# i2c-4x8matrix-relays.net
KiCad netlist of a schematic drawn in EAGLE
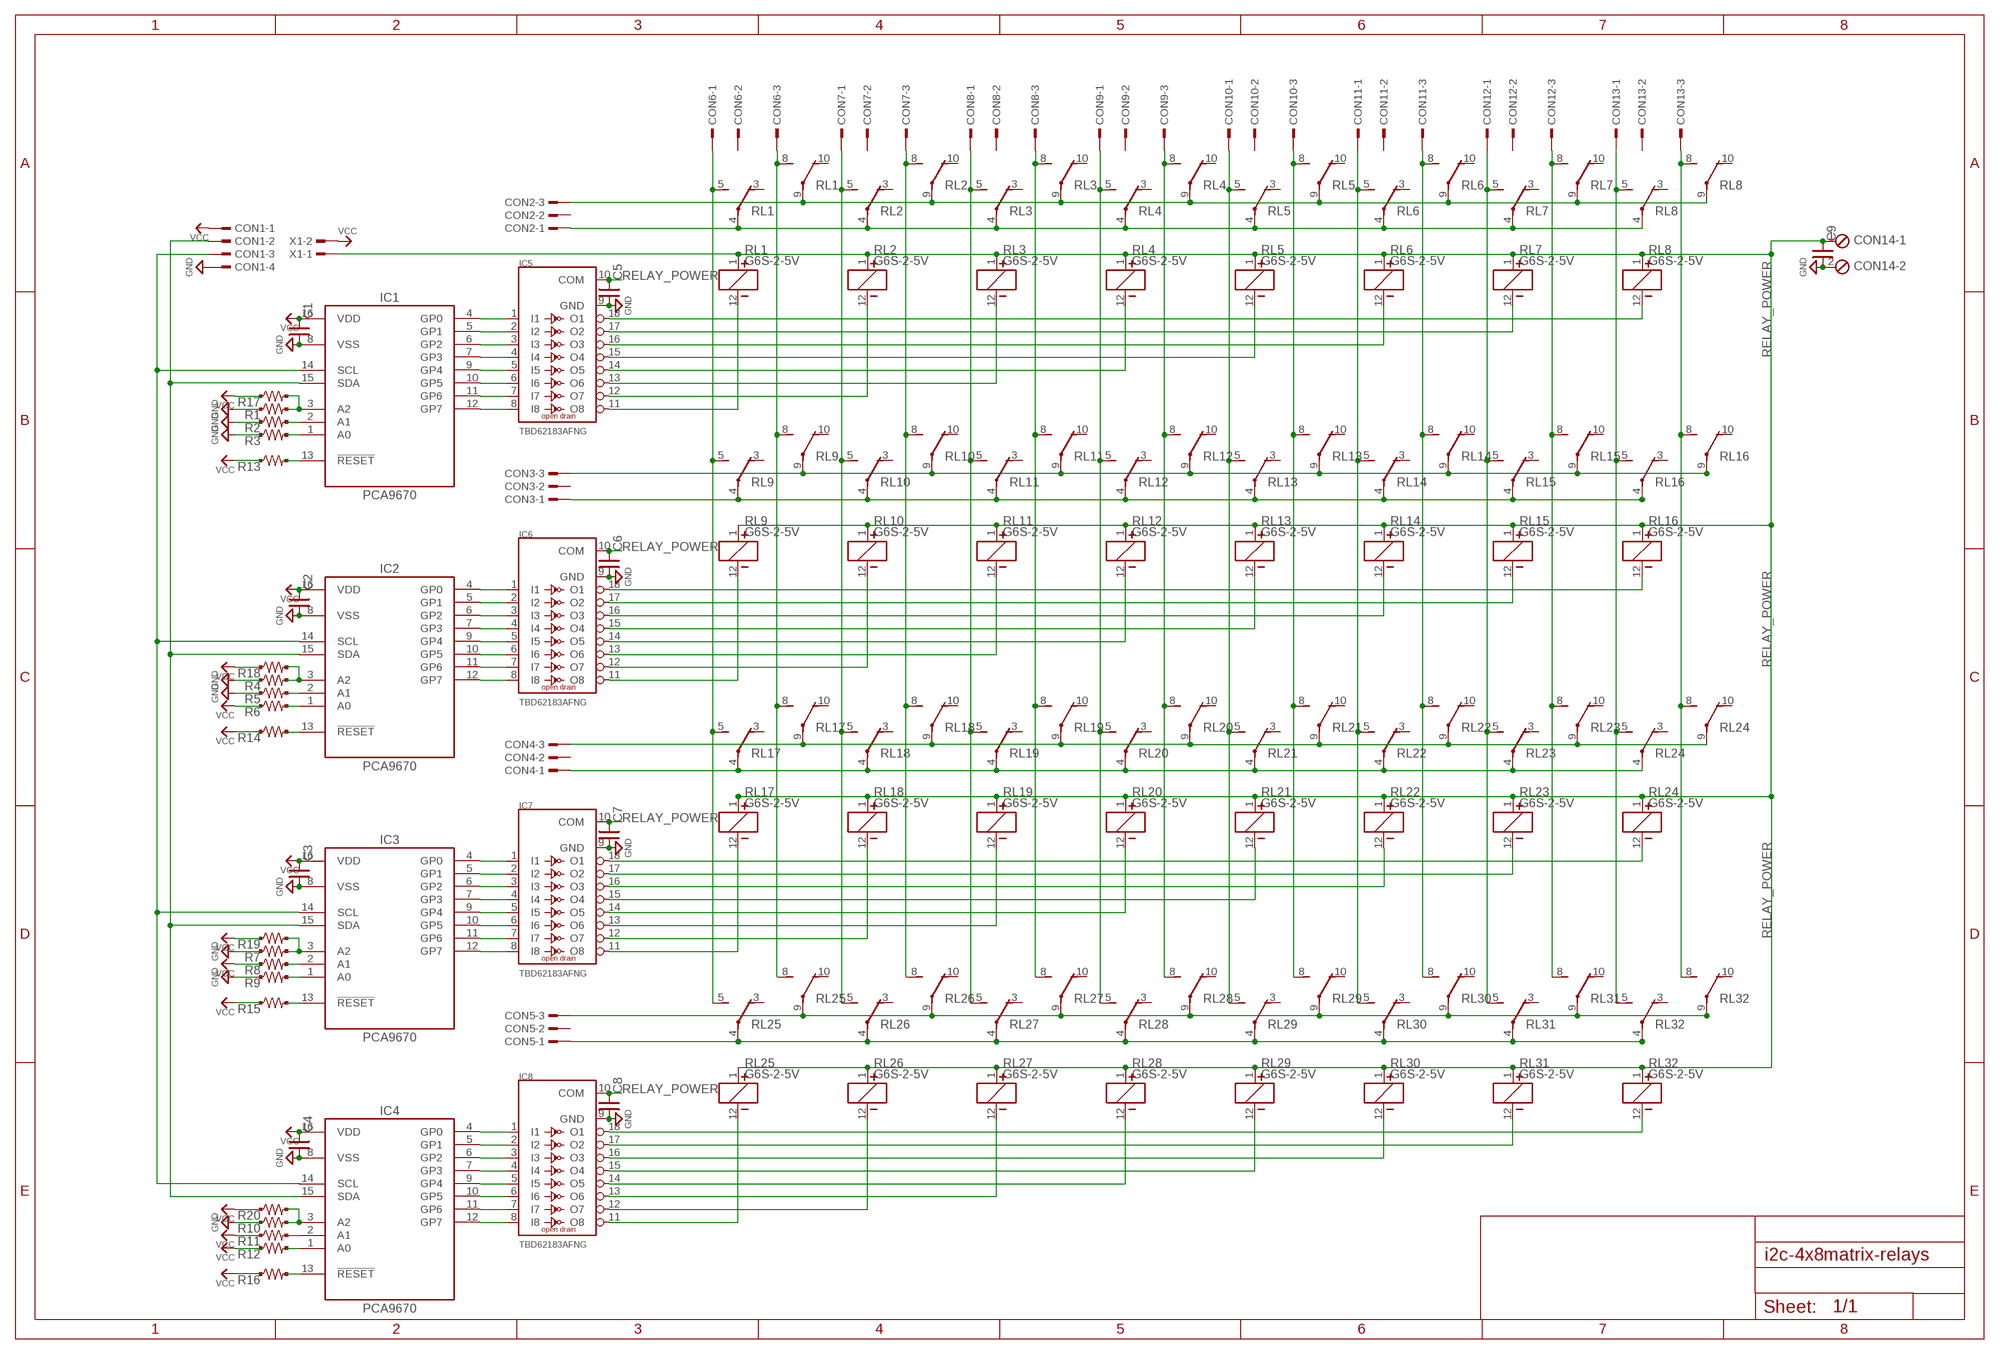
[diagram p0: schematic, sheet 1]

(export (version "E")
  (design (tool "Eeschema 10.0.6"))
  (components
    (comp (ref "C1")
      (value "C-SMD-0.1U-1005")
      (footprint "eagle-import:C0402")
      (libsource (lib "eagle-import") (part "C-SMD--10050.1U"))
    )
    (comp (ref "C2")
      (value "C-SMD-0.1U-1005")
      (footprint "eagle-import:C0402")
      (libsource (lib "eagle-import") (part "C-SMD--10050.1U"))
    )
    (comp (ref "C3")
      (value "C-SMD-0.1U-1005")
      (footprint "eagle-import:C0402")
      (libsource (lib "eagle-import") (part "C-SMD--10050.1U"))
    )
    (comp (ref "C4")
      (value "C-SMD-0.1U-1005")
      (footprint "eagle-import:C0402")
      (libsource (lib "eagle-import") (part "C-SMD--10050.1U"))
    )
    (comp (ref "C5")
      (value "C-SMD-0.1U-1005")
      (footprint "eagle-import:C0402")
      (libsource (lib "eagle-import") (part "C-SMD--10050.1U"))
    )
    (comp (ref "C6")
      (value "C-SMD-0.1U-1005")
      (footprint "eagle-import:C0402")
      (libsource (lib "eagle-import") (part "C-SMD--10050.1U"))
    )
    (comp (ref "C7")
      (value "C-SMD-0.1U-1005")
      (footprint "eagle-import:C0402")
      (libsource (lib "eagle-import") (part "C-SMD--10050.1U"))
    )
    (comp (ref "C8")
      (value "C-SMD-0.1U-1005")
      (footprint "eagle-import:C0402")
      (libsource (lib "eagle-import") (part "C-SMD--10050.1U"))
    )
    (comp (ref "C9")
      (value "C-SMD-10U-1608")
      (footprint "eagle-import:CR-1608")
      (libsource (lib "eagle-import") (part "C-SMD--160810U"))
    )
    (comp (ref "CON1")
      (value "S4B-XH-A")
      (footprint "eagle-import:S4B-XH-A(LF)(SN)")
      (libsource (lib "eagle-import") (part "S4B-XH-A"))
    )
    (comp (ref "CON2")
      (value "S3B-XH-A")
      (footprint "eagle-import:S3B-XH-A(LF)(SN)")
      (libsource (lib "eagle-import") (part "S3B-XH-A"))
    )
    (comp (ref "CON3")
      (value "S3B-XH-A")
      (footprint "eagle-import:S3B-XH-A(LF)(SN)")
      (libsource (lib "eagle-import") (part "S3B-XH-A"))
    )
    (comp (ref "CON4")
      (value "S3B-XH-A")
      (footprint "eagle-import:S3B-XH-A(LF)(SN)")
      (libsource (lib "eagle-import") (part "S3B-XH-A"))
    )
    (comp (ref "CON5")
      (value "S3B-XH-A")
      (footprint "eagle-import:S3B-XH-A(LF)(SN)")
      (libsource (lib "eagle-import") (part "S3B-XH-A"))
    )
    (comp (ref "CON6")
      (value "S3B-XH-A")
      (footprint "eagle-import:S3B-XH-A(LF)(SN)")
      (libsource (lib "eagle-import") (part "S3B-XH-A"))
    )
    (comp (ref "CON7")
      (value "S3B-XH-A")
      (footprint "eagle-import:S3B-XH-A(LF)(SN)")
      (libsource (lib "eagle-import") (part "S3B-XH-A"))
    )
    (comp (ref "CON8")
      (value "S3B-XH-A")
      (footprint "eagle-import:S3B-XH-A(LF)(SN)")
      (libsource (lib "eagle-import") (part "S3B-XH-A"))
    )
    (comp (ref "CON9")
      (value "S3B-XH-A")
      (footprint "eagle-import:S3B-XH-A(LF)(SN)")
      (libsource (lib "eagle-import") (part "S3B-XH-A"))
    )
    (comp (ref "CON10")
      (value "S3B-XH-A")
      (footprint "eagle-import:S3B-XH-A(LF)(SN)")
      (libsource (lib "eagle-import") (part "S3B-XH-A"))
    )
    (comp (ref "CON11")
      (value "S3B-XH-A")
      (footprint "eagle-import:S3B-XH-A(LF)(SN)")
      (libsource (lib "eagle-import") (part "S3B-XH-A"))
    )
    (comp (ref "CON12")
      (value "S3B-XH-A")
      (footprint "eagle-import:S3B-XH-A(LF)(SN)")
      (libsource (lib "eagle-import") (part "S3B-XH-A"))
    )
    (comp (ref "CON13")
      (value "S3B-XH-A")
      (footprint "eagle-import:S3B-XH-A(LF)(SN)")
      (libsource (lib "eagle-import") (part "S3B-XH-A"))
    )
    (comp (ref "CON14")
      (value "ETB43024B")
      (footprint "eagle-import:ETB43024")
      (libsource (lib "eagle-import") (part "ETB43024B"))
    )
    (comp (ref "IC1")
      (value "PCA9670")
      (footprint "eagle-import:SOT65P510X450X110-16N")
      (libsource (lib "eagle-import") (part "PCA9670"))
    )
    (comp (ref "IC2")
      (value "PCA9670")
      (footprint "eagle-import:SOT65P510X450X110-16N")
      (libsource (lib "eagle-import") (part "PCA9670"))
    )
    (comp (ref "IC3")
      (value "PCA9670")
      (footprint "eagle-import:SOT65P510X450X110-16N")
      (libsource (lib "eagle-import") (part "PCA9670"))
    )
    (comp (ref "IC4")
      (value "PCA9670")
      (footprint "eagle-import:SOT65P510X450X110-16N")
      (libsource (lib "eagle-import") (part "PCA9670"))
    )
    (comp (ref "IC5")
      (value "TBD62183AFNG")
      (footprint "eagle-import:SOT65P640X440-18N")
      (libsource (lib "eagle-import") (part "TBD62183AFNG"))
    )
    (comp (ref "IC6")
      (value "TBD62183AFNG")
      (footprint "eagle-import:SOT65P640X440-18N")
      (libsource (lib "eagle-import") (part "TBD62183AFNG"))
    )
    (comp (ref "IC7")
      (value "TBD62183AFNG")
      (footprint "eagle-import:SOT65P640X440-18N")
      (libsource (lib "eagle-import") (part "TBD62183AFNG"))
    )
    (comp (ref "IC8")
      (value "TBD62183AFNG")
      (footprint "eagle-import:SOT65P640X440-18N")
      (libsource (lib "eagle-import") (part "TBD62183AFNG"))
    )
    (comp (ref "R1")
      (value "R-US--1005SHORT")
      (footprint "eagle-import:R0402SHORT")
      (libsource (lib "eagle-import") (part "R-US--1005SHORT"))
    )
    (comp (ref "R2")
      (value "R-US--1005SHORT")
      (footprint "eagle-import:R0402SHORT")
      (libsource (lib "eagle-import") (part "R-US--1005SHORT"))
    )
    (comp (ref "R3")
      (value "R-US--1005SHORT")
      (footprint "eagle-import:R0402SHORT")
      (libsource (lib "eagle-import") (part "R-US--1005SHORT"))
    )
    (comp (ref "R4")
      (value "R-US--1005SHORT")
      (footprint "eagle-import:R0402SHORT")
      (libsource (lib "eagle-import") (part "R-US--1005SHORT"))
    )
    (comp (ref "R5")
      (value "R-US--1005SHORT")
      (footprint "eagle-import:R0402SHORT")
      (libsource (lib "eagle-import") (part "R-US--1005SHORT"))
    )
    (comp (ref "R6")
      (value "R-US--1005SHORT")
      (footprint "eagle-import:R0402SHORT")
      (libsource (lib "eagle-import") (part "R-US--1005SHORT"))
    )
    (comp (ref "R7")
      (value "R-US--1005SHORT")
      (footprint "eagle-import:R0402SHORT")
      (libsource (lib "eagle-import") (part "R-US--1005SHORT"))
    )
    (comp (ref "R8")
      (value "R-US--1005SHORT")
      (footprint "eagle-import:R0402SHORT")
      (libsource (lib "eagle-import") (part "R-US--1005SHORT"))
    )
    (comp (ref "R9")
      (value "R-US--1005SHORT")
      (footprint "eagle-import:R0402SHORT")
      (libsource (lib "eagle-import") (part "R-US--1005SHORT"))
    )
    (comp (ref "R10")
      (value "R-US--1005SHORT")
      (footprint "eagle-import:R0402SHORT")
      (libsource (lib "eagle-import") (part "R-US--1005SHORT"))
    )
    (comp (ref "R11")
      (value "R-US--1005SHORT")
      (footprint "eagle-import:R0402SHORT")
      (libsource (lib "eagle-import") (part "R-US--1005SHORT"))
    )
    (comp (ref "R12")
      (value "R-US--1005SHORT")
      (footprint "eagle-import:R0402SHORT")
      (libsource (lib "eagle-import") (part "R-US--1005SHORT"))
    )
    (comp (ref "R13")
      (value "R-US--1005SHORT")
      (footprint "eagle-import:R0402SHORT")
      (libsource (lib "eagle-import") (part "R-US--1005SHORT"))
    )
    (comp (ref "R14")
      (value "R-US--1005SHORT")
      (footprint "eagle-import:R0402SHORT")
      (libsource (lib "eagle-import") (part "R-US--1005SHORT"))
    )
    (comp (ref "R15")
      (value "R-US--1005SHORT")
      (footprint "eagle-import:R0402SHORT")
      (libsource (lib "eagle-import") (part "R-US--1005SHORT"))
    )
    (comp (ref "R16")
      (value "R-US--1005SHORT")
      (footprint "eagle-import:R0402SHORT")
      (libsource (lib "eagle-import") (part "R-US--1005SHORT"))
    )
    (comp (ref "R17")
      (value "R-US-10K-1005")
      (footprint "eagle-import:C0402")
      (libsource (lib "eagle-import") (part "R-US--100510K"))
    )
    (comp (ref "R18")
      (value "R-US-10K-1005")
      (footprint "eagle-import:C0402")
      (libsource (lib "eagle-import") (part "R-US--100510K"))
    )
    (comp (ref "R19")
      (value "R-US-10K-1005")
      (footprint "eagle-import:C0402")
      (libsource (lib "eagle-import") (part "R-US--100510K"))
    )
    (comp (ref "R20")
      (value "R-US-10K-1005")
      (footprint "eagle-import:C0402")
      (libsource (lib "eagle-import") (part "R-US--100510K"))
    )
    (comp (ref "RL1")
      (value "G6S-2-5V")
      (footprint "eagle-import:G6S-2")
      (libsource (lib "eagle-import") (part "G6S-2-5V"))
    )
    (comp (ref "RL2")
      (value "G6S-2-5V")
      (footprint "eagle-import:G6S-2")
      (libsource (lib "eagle-import") (part "G6S-2-5V"))
    )
    (comp (ref "RL3")
      (value "G6S-2-5V")
      (footprint "eagle-import:G6S-2")
      (libsource (lib "eagle-import") (part "G6S-2-5V"))
    )
    (comp (ref "RL4")
      (value "G6S-2-5V")
      (footprint "eagle-import:G6S-2")
      (libsource (lib "eagle-import") (part "G6S-2-5V"))
    )
    (comp (ref "RL5")
      (value "G6S-2-5V")
      (footprint "eagle-import:G6S-2")
      (libsource (lib "eagle-import") (part "G6S-2-5V"))
    )
    (comp (ref "RL6")
      (value "G6S-2-5V")
      (footprint "eagle-import:G6S-2")
      (libsource (lib "eagle-import") (part "G6S-2-5V"))
    )
    (comp (ref "RL7")
      (value "G6S-2-5V")
      (footprint "eagle-import:G6S-2")
      (libsource (lib "eagle-import") (part "G6S-2-5V"))
    )
    (comp (ref "RL8")
      (value "G6S-2-5V")
      (footprint "eagle-import:G6S-2")
      (libsource (lib "eagle-import") (part "G6S-2-5V"))
    )
    (comp (ref "RL9")
      (value "G6S-2-5V")
      (footprint "eagle-import:G6S-2")
      (libsource (lib "eagle-import") (part "G6S-2-5V"))
    )
    (comp (ref "RL10")
      (value "G6S-2-5V")
      (footprint "eagle-import:G6S-2")
      (libsource (lib "eagle-import") (part "G6S-2-5V"))
    )
    (comp (ref "RL11")
      (value "G6S-2-5V")
      (footprint "eagle-import:G6S-2")
      (libsource (lib "eagle-import") (part "G6S-2-5V"))
    )
    (comp (ref "RL12")
      (value "G6S-2-5V")
      (footprint "eagle-import:G6S-2")
      (libsource (lib "eagle-import") (part "G6S-2-5V"))
    )
    (comp (ref "RL13")
      (value "G6S-2-5V")
      (footprint "eagle-import:G6S-2")
      (libsource (lib "eagle-import") (part "G6S-2-5V"))
    )
    (comp (ref "RL14")
      (value "G6S-2-5V")
      (footprint "eagle-import:G6S-2")
      (libsource (lib "eagle-import") (part "G6S-2-5V"))
    )
    (comp (ref "RL15")
      (value "G6S-2-5V")
      (footprint "eagle-import:G6S-2")
      (libsource (lib "eagle-import") (part "G6S-2-5V"))
    )
    (comp (ref "RL16")
      (value "G6S-2-5V")
      (footprint "eagle-import:G6S-2")
      (libsource (lib "eagle-import") (part "G6S-2-5V"))
    )
    (comp (ref "RL17")
      (value "G6S-2-5V")
      (footprint "eagle-import:G6S-2")
      (libsource (lib "eagle-import") (part "G6S-2-5V"))
    )
    (comp (ref "RL18")
      (value "G6S-2-5V")
      (footprint "eagle-import:G6S-2")
      (libsource (lib "eagle-import") (part "G6S-2-5V"))
    )
    (comp (ref "RL19")
      (value "G6S-2-5V")
      (footprint "eagle-import:G6S-2")
      (libsource (lib "eagle-import") (part "G6S-2-5V"))
    )
    (comp (ref "RL20")
      (value "G6S-2-5V")
      (footprint "eagle-import:G6S-2")
      (libsource (lib "eagle-import") (part "G6S-2-5V"))
    )
    (comp (ref "RL21")
      (value "G6S-2-5V")
      (footprint "eagle-import:G6S-2")
      (libsource (lib "eagle-import") (part "G6S-2-5V"))
    )
    (comp (ref "RL22")
      (value "G6S-2-5V")
      (footprint "eagle-import:G6S-2")
      (libsource (lib "eagle-import") (part "G6S-2-5V"))
    )
    (comp (ref "RL23")
      (value "G6S-2-5V")
      (footprint "eagle-import:G6S-2")
      (libsource (lib "eagle-import") (part "G6S-2-5V"))
    )
    (comp (ref "RL24")
      (value "G6S-2-5V")
      (footprint "eagle-import:G6S-2")
      (libsource (lib "eagle-import") (part "G6S-2-5V"))
    )
    (comp (ref "RL25")
      (value "G6S-2-5V")
      (footprint "eagle-import:G6S-2")
      (libsource (lib "eagle-import") (part "G6S-2-5V"))
    )
    (comp (ref "RL26")
      (value "G6S-2-5V")
      (footprint "eagle-import:G6S-2")
      (libsource (lib "eagle-import") (part "G6S-2-5V"))
    )
    (comp (ref "RL27")
      (value "G6S-2-5V")
      (footprint "eagle-import:G6S-2")
      (libsource (lib "eagle-import") (part "G6S-2-5V"))
    )
    (comp (ref "RL28")
      (value "G6S-2-5V")
      (footprint "eagle-import:G6S-2")
      (libsource (lib "eagle-import") (part "G6S-2-5V"))
    )
    (comp (ref "RL29")
      (value "G6S-2-5V")
      (footprint "eagle-import:G6S-2")
      (libsource (lib "eagle-import") (part "G6S-2-5V"))
    )
    (comp (ref "RL30")
      (value "G6S-2-5V")
      (footprint "eagle-import:G6S-2")
      (libsource (lib "eagle-import") (part "G6S-2-5V"))
    )
    (comp (ref "RL31")
      (value "G6S-2-5V")
      (footprint "eagle-import:G6S-2")
      (libsource (lib "eagle-import") (part "G6S-2-5V"))
    )
    (comp (ref "RL32")
      (value "G6S-2-5V")
      (footprint "eagle-import:G6S-2")
      (libsource (lib "eagle-import") (part "G6S-2-5V"))
    )
    (comp (ref "X1")
      (value "PH-1X2SG")
      (footprint "eagle-import:PH-1X2SG")
      (libsource (lib "eagle-import") (part "PH-1X2SG"))
    )
  )
  (nets
    (net (code "1") (name "/RELAY_POWER") (class "Default")
      (node (ref "C5") (pin "1") (pinfunction "1_1") (pintype "passive"))
      (node (ref "C6") (pin "1") (pinfunction "1_1") (pintype "passive"))
      (node (ref "C7") (pin "1") (pinfunction "1_1") (pintype "passive"))
      (node (ref "C8") (pin "1") (pinfunction "1_1") (pintype "passive"))
      (node (ref "C9") (pin "1") (pinfunction "1_1") (pintype "passive"))
      (node (ref "CON14") (pin "1") (pinfunction "1_1") (pintype "passive"))
      (node (ref "IC5") (pin "10") (pinfunction "COM_10") (pintype "power_in"))
      (node (ref "IC6") (pin "10") (pinfunction "COM_10") (pintype "power_in"))
      (node (ref "IC7") (pin "10") (pinfunction "COM_10") (pintype "power_in"))
      (node (ref "IC8") (pin "10") (pinfunction "COM_10") (pintype "power_in"))
      (node (ref "RL1") (pin "1") (pinfunction "1_1") (pintype "passive"))
      (node (ref "RL10") (pin "1") (pinfunction "1_1") (pintype "passive"))
      (node (ref "RL11") (pin "1") (pinfunction "1_1") (pintype "passive"))
      (node (ref "RL12") (pin "1") (pinfunction "1_1") (pintype "passive"))
      (node (ref "RL13") (pin "1") (pinfunction "1_1") (pintype "passive"))
      (node (ref "RL14") (pin "1") (pinfunction "1_1") (pintype "passive"))
      (node (ref "RL15") (pin "1") (pinfunction "1_1") (pintype "passive"))
      (node (ref "RL16") (pin "1") (pinfunction "1_1") (pintype "passive"))
      (node (ref "RL17") (pin "1") (pinfunction "1_1") (pintype "passive"))
      (node (ref "RL18") (pin "1") (pinfunction "1_1") (pintype "passive"))
      (node (ref "RL19") (pin "1") (pinfunction "1_1") (pintype "passive"))
      (node (ref "RL2") (pin "1") (pinfunction "1_1") (pintype "passive"))
      (node (ref "RL20") (pin "1") (pinfunction "1_1") (pintype "passive"))
      (node (ref "RL21") (pin "1") (pinfunction "1_1") (pintype "passive"))
      (node (ref "RL22") (pin "1") (pinfunction "1_1") (pintype "passive"))
      (node (ref "RL23") (pin "1") (pinfunction "1_1") (pintype "passive"))
      (node (ref "RL24") (pin "1") (pinfunction "1_1") (pintype "passive"))
      (node (ref "RL25") (pin "1") (pinfunction "1_1") (pintype "passive"))
      (node (ref "RL26") (pin "1") (pinfunction "1_1") (pintype "passive"))
      (node (ref "RL27") (pin "1") (pinfunction "1_1") (pintype "passive"))
      (node (ref "RL28") (pin "1") (pinfunction "1_1") (pintype "passive"))
      (node (ref "RL29") (pin "1") (pinfunction "1_1") (pintype "passive"))
      (node (ref "RL3") (pin "1") (pinfunction "1_1") (pintype "passive"))
      (node (ref "RL30") (pin "1") (pinfunction "1_1") (pintype "passive"))
      (node (ref "RL31") (pin "1") (pinfunction "1_1") (pintype "passive"))
      (node (ref "RL32") (pin "1") (pinfunction "1_1") (pintype "passive"))
      (node (ref "RL4") (pin "1") (pinfunction "1_1") (pintype "passive"))
      (node (ref "RL5") (pin "1") (pinfunction "1_1") (pintype "passive"))
      (node (ref "RL6") (pin "1") (pinfunction "1_1") (pintype "passive"))
      (node (ref "RL7") (pin "1") (pinfunction "1_1") (pintype "passive"))
      (node (ref "RL8") (pin "1") (pinfunction "1_1") (pintype "passive"))
      (node (ref "RL9") (pin "1") (pinfunction "1_1") (pintype "passive"))
      (node (ref "X1") (pin "1") (pinfunction "1_1") (pintype "passive"))
    )
    (net (code "2") (name "GND") (class "Default")
      (node (ref "C1") (pin "2") (pinfunction "2_2") (pintype "passive"))
      (node (ref "C2") (pin "2") (pinfunction "2_2") (pintype "passive"))
      (node (ref "C3") (pin "2") (pinfunction "2_2") (pintype "passive"))
      (node (ref "C4") (pin "2") (pinfunction "2_2") (pintype "passive"))
      (node (ref "C5") (pin "2") (pinfunction "2_2") (pintype "passive"))
      (node (ref "C6") (pin "2") (pinfunction "2_2") (pintype "passive"))
      (node (ref "C7") (pin "2") (pinfunction "2_2") (pintype "passive"))
      (node (ref "C8") (pin "2") (pinfunction "2_2") (pintype "passive"))
      (node (ref "C9") (pin "2") (pinfunction "2_2") (pintype "passive"))
      (node (ref "CON1") (pin "4") (pinfunction "1_4") (pintype "passive"))
      (node (ref "CON14") (pin "2") (pinfunction "1_2") (pintype "passive"))
      (node (ref "IC1") (pin "8") (pinfunction "VSS_8") (pintype "power_in"))
      (node (ref "IC2") (pin "8") (pinfunction "VSS_8") (pintype "power_in"))
      (node (ref "IC3") (pin "8") (pinfunction "VSS_8") (pintype "power_in"))
      (node (ref "IC4") (pin "8") (pinfunction "VSS_8") (pintype "power_in"))
      (node (ref "IC5") (pin "9") (pinfunction "GND_9") (pintype "power_in"))
      (node (ref "IC6") (pin "9") (pinfunction "GND_9") (pintype "power_in"))
      (node (ref "IC7") (pin "9") (pinfunction "GND_9") (pintype "power_in"))
      (node (ref "IC8") (pin "9") (pinfunction "GND_9") (pintype "power_in"))
      (node (ref "R1") (pin "1") (pinfunction "1_1") (pintype "passive"))
      (node (ref "R1") (pin "2") (pinfunction "1_2") (pintype "passive"))
      (node (ref "R10") (pin "1") (pinfunction "1_1") (pintype "passive"))
      (node (ref "R10") (pin "2") (pinfunction "1_2") (pintype "passive"))
      (node (ref "R2") (pin "1") (pinfunction "1_1") (pintype "passive"))
      (node (ref "R2") (pin "2") (pinfunction "1_2") (pintype "passive"))
      (node (ref "R3") (pin "1") (pinfunction "1_1") (pintype "passive"))
      (node (ref "R3") (pin "2") (pinfunction "1_2") (pintype "passive"))
      (node (ref "R4") (pin "1") (pinfunction "1_1") (pintype "passive"))
      (node (ref "R4") (pin "2") (pinfunction "1_2") (pintype "passive"))
      (node (ref "R5") (pin "1") (pinfunction "1_1") (pintype "passive"))
      (node (ref "R5") (pin "2") (pinfunction "1_2") (pintype "passive"))
      (node (ref "R7") (pin "1") (pinfunction "1_1") (pintype "passive"))
      (node (ref "R7") (pin "2") (pinfunction "1_2") (pintype "passive"))
      (node (ref "R9") (pin "1") (pinfunction "1_1") (pintype "passive"))
      (node (ref "R9") (pin "2") (pinfunction "1_2") (pintype "passive"))
    )
    (net (code "3") (name "Net-(CON1B-1)") (class "Default")
      (node (ref "CON1") (pin "2") (pinfunction "1_2") (pintype "passive"))
      (node (ref "IC1") (pin "15") (pinfunction "SDA_15") (pintype "bidirectional"))
      (node (ref "IC2") (pin "15") (pinfunction "SDA_15") (pintype "bidirectional"))
      (node (ref "IC3") (pin "15") (pinfunction "SDA_15") (pintype "bidirectional"))
      (node (ref "IC4") (pin "15") (pinfunction "SDA_15") (pintype "bidirectional"))
    )
    (net (code "4") (name "Net-(CON1C-1)") (class "Default")
      (node (ref "CON1") (pin "3") (pinfunction "1_3") (pintype "passive"))
      (node (ref "IC1") (pin "14") (pinfunction "SCL_14") (pintype "bidirectional"))
      (node (ref "IC2") (pin "14") (pinfunction "SCL_14") (pintype "bidirectional"))
      (node (ref "IC3") (pin "14") (pinfunction "SCL_14") (pintype "bidirectional"))
      (node (ref "IC4") (pin "14") (pinfunction "SCL_14") (pintype "bidirectional"))
    )
    (net (code "5") (name "Net-(CON2C-1)") (class "Default")
      (node (ref "CON2") (pin "3") (pinfunction "1_3") (pintype "passive"))
      (node (ref "RL1") (pin "9") (pinfunction "COM_9") (pintype "passive"))
      (node (ref "RL2") (pin "9") (pinfunction "COM_9") (pintype "passive"))
      (node (ref "RL3") (pin "9") (pinfunction "COM_9") (pintype "passive"))
      (node (ref "RL4") (pin "9") (pinfunction "COM_9") (pintype "passive"))
      (node (ref "RL5") (pin "9") (pinfunction "COM_9") (pintype "passive"))
      (node (ref "RL6") (pin "9") (pinfunction "COM_9") (pintype "passive"))
      (node (ref "RL7") (pin "9") (pinfunction "COM_9") (pintype "passive"))
      (node (ref "RL8") (pin "9") (pinfunction "COM_9") (pintype "passive"))
    )
    (net (code "6") (name "Net-(CON3C-1)") (class "Default")
      (node (ref "CON3") (pin "3") (pinfunction "1_3") (pintype "passive"))
      (node (ref "RL10") (pin "9") (pinfunction "COM_9") (pintype "passive"))
      (node (ref "RL11") (pin "9") (pinfunction "COM_9") (pintype "passive"))
      (node (ref "RL12") (pin "9") (pinfunction "COM_9") (pintype "passive"))
      (node (ref "RL13") (pin "9") (pinfunction "COM_9") (pintype "passive"))
      (node (ref "RL14") (pin "9") (pinfunction "COM_9") (pintype "passive"))
      (node (ref "RL15") (pin "9") (pinfunction "COM_9") (pintype "passive"))
      (node (ref "RL16") (pin "9") (pinfunction "COM_9") (pintype "passive"))
      (node (ref "RL9") (pin "9") (pinfunction "COM_9") (pintype "passive"))
    )
    (net (code "7") (name "Net-(CON4C-1)") (class "Default")
      (node (ref "CON4") (pin "3") (pinfunction "1_3") (pintype "passive"))
      (node (ref "RL17") (pin "9") (pinfunction "COM_9") (pintype "passive"))
      (node (ref "RL18") (pin "9") (pinfunction "COM_9") (pintype "passive"))
      (node (ref "RL19") (pin "9") (pinfunction "COM_9") (pintype "passive"))
      (node (ref "RL20") (pin "9") (pinfunction "COM_9") (pintype "passive"))
      (node (ref "RL21") (pin "9") (pinfunction "COM_9") (pintype "passive"))
      (node (ref "RL22") (pin "9") (pinfunction "COM_9") (pintype "passive"))
      (node (ref "RL23") (pin "9") (pinfunction "COM_9") (pintype "passive"))
      (node (ref "RL24") (pin "9") (pinfunction "COM_9") (pintype "passive"))
    )
    (net (code "8") (name "Net-(CON5C-1)") (class "Default")
      (node (ref "CON5") (pin "3") (pinfunction "1_3") (pintype "passive"))
      (node (ref "RL25") (pin "9") (pinfunction "COM_9") (pintype "passive"))
      (node (ref "RL26") (pin "9") (pinfunction "COM_9") (pintype "passive"))
      (node (ref "RL27") (pin "9") (pinfunction "COM_9") (pintype "passive"))
      (node (ref "RL28") (pin "9") (pinfunction "COM_9") (pintype "passive"))
      (node (ref "RL29") (pin "9") (pinfunction "COM_9") (pintype "passive"))
      (node (ref "RL30") (pin "9") (pinfunction "COM_9") (pintype "passive"))
      (node (ref "RL31") (pin "9") (pinfunction "COM_9") (pintype "passive"))
      (node (ref "RL32") (pin "9") (pinfunction "COM_9") (pintype "passive"))
    )
    (net (code "9") (name "Net-(CON6C-1)") (class "Default")
      (node (ref "CON6") (pin "3") (pinfunction "1_3") (pintype "passive"))
      (node (ref "RL1") (pin "8") (pinfunction "NO_8") (pintype "passive"))
      (node (ref "RL17") (pin "8") (pinfunction "NO_8") (pintype "passive"))
      (node (ref "RL25") (pin "8") (pinfunction "NO_8") (pintype "passive"))
      (node (ref "RL9") (pin "8") (pinfunction "NO_8") (pintype "passive"))
    )
    (net (code "10") (name "Net-(CON7C-1)") (class "Default")
      (node (ref "CON7") (pin "3") (pinfunction "1_3") (pintype "passive"))
      (node (ref "RL10") (pin "8") (pinfunction "NO_8") (pintype "passive"))
      (node (ref "RL18") (pin "8") (pinfunction "NO_8") (pintype "passive"))
      (node (ref "RL2") (pin "8") (pinfunction "NO_8") (pintype "passive"))
      (node (ref "RL26") (pin "8") (pinfunction "NO_8") (pintype "passive"))
    )
    (net (code "11") (name "Net-(CON8C-1)") (class "Default")
      (node (ref "CON8") (pin "3") (pinfunction "1_3") (pintype "passive"))
      (node (ref "RL11") (pin "8") (pinfunction "NO_8") (pintype "passive"))
      (node (ref "RL19") (pin "8") (pinfunction "NO_8") (pintype "passive"))
      (node (ref "RL27") (pin "8") (pinfunction "NO_8") (pintype "passive"))
      (node (ref "RL3") (pin "8") (pinfunction "NO_8") (pintype "passive"))
    )
    (net (code "12") (name "Net-(CON9C-1)") (class "Default")
      (node (ref "CON9") (pin "3") (pinfunction "1_3") (pintype "passive"))
      (node (ref "RL12") (pin "8") (pinfunction "NO_8") (pintype "passive"))
      (node (ref "RL20") (pin "8") (pinfunction "NO_8") (pintype "passive"))
      (node (ref "RL28") (pin "8") (pinfunction "NO_8") (pintype "passive"))
      (node (ref "RL4") (pin "8") (pinfunction "NO_8") (pintype "passive"))
    )
    (net (code "13") (name "Net-(CON10C-1)") (class "Default")
      (node (ref "CON10") (pin "3") (pinfunction "1_3") (pintype "passive"))
      (node (ref "RL13") (pin "8") (pinfunction "NO_8") (pintype "passive"))
      (node (ref "RL21") (pin "8") (pinfunction "NO_8") (pintype "passive"))
      (node (ref "RL29") (pin "8") (pinfunction "NO_8") (pintype "passive"))
      (node (ref "RL5") (pin "8") (pinfunction "NO_8") (pintype "passive"))
    )
    (net (code "14") (name "Net-(CON11C-1)") (class "Default")
      (node (ref "CON11") (pin "3") (pinfunction "1_3") (pintype "passive"))
      (node (ref "RL14") (pin "8") (pinfunction "NO_8") (pintype "passive"))
      (node (ref "RL22") (pin "8") (pinfunction "NO_8") (pintype "passive"))
      (node (ref "RL30") (pin "8") (pinfunction "NO_8") (pintype "passive"))
      (node (ref "RL6") (pin "8") (pinfunction "NO_8") (pintype "passive"))
    )
    (net (code "15") (name "Net-(CON12C-1)") (class "Default")
      (node (ref "CON12") (pin "3") (pinfunction "1_3") (pintype "passive"))
      (node (ref "RL15") (pin "8") (pinfunction "NO_8") (pintype "passive"))
      (node (ref "RL23") (pin "8") (pinfunction "NO_8") (pintype "passive"))
      (node (ref "RL31") (pin "8") (pinfunction "NO_8") (pintype "passive"))
      (node (ref "RL7") (pin "8") (pinfunction "NO_8") (pintype "passive"))
    )
    (net (code "16") (name "Net-(CON13C-1)") (class "Default")
      (node (ref "CON13") (pin "3") (pinfunction "1_3") (pintype "passive"))
      (node (ref "RL16") (pin "8") (pinfunction "NO_8") (pintype "passive"))
      (node (ref "RL24") (pin "8") (pinfunction "NO_8") (pintype "passive"))
      (node (ref "RL32") (pin "8") (pinfunction "NO_8") (pintype "passive"))
      (node (ref "RL8") (pin "8") (pinfunction "NO_8") (pintype "passive"))
    )
    (net (code "17") (name "Net-(IC1-A0)") (class "Default")
      (node (ref "IC1") (pin "1") (pinfunction "A0_1") (pintype "bidirectional"))
      (node (ref "R3") (pin "3") (pinfunction "2_3") (pintype "passive"))
    )
    (net (code "18") (name "Net-(IC1-A1)") (class "Default")
      (node (ref "IC1") (pin "2") (pinfunction "A1_2") (pintype "bidirectional"))
      (node (ref "R2") (pin "3") (pinfunction "2_3") (pintype "passive"))
    )
    (net (code "19") (name "Net-(IC1-A2)") (class "Default")
      (node (ref "IC1") (pin "3") (pinfunction "A2_3") (pintype "bidirectional"))
      (node (ref "R1") (pin "3") (pinfunction "2_3") (pintype "passive"))
      (node (ref "R17") (pin "2") (pinfunction "2_2") (pintype "passive"))
    )
    (net (code "20") (name "Net-(IC1-GP0)") (class "Default")
      (node (ref "IC1") (pin "4") (pinfunction "GP0_4") (pintype "bidirectional"))
      (node (ref "IC5") (pin "1") (pinfunction "I1_1") (pintype "bidirectional"))
    )
    (net (code "21") (name "Net-(IC1-GP1)") (class "Default")
      (node (ref "IC1") (pin "5") (pinfunction "GP1_5") (pintype "bidirectional"))
      (node (ref "IC5") (pin "2") (pinfunction "I2_2") (pintype "bidirectional"))
    )
    (net (code "22") (name "Net-(IC1-GP2)") (class "Default")
      (node (ref "IC1") (pin "6") (pinfunction "GP2_6") (pintype "bidirectional"))
      (node (ref "IC5") (pin "3") (pinfunction "I3_3") (pintype "bidirectional"))
    )
    (net (code "23") (name "Net-(IC1-GP3)") (class "Default")
      (node (ref "IC1") (pin "7") (pinfunction "GP3_7") (pintype "bidirectional"))
      (node (ref "IC5") (pin "4") (pinfunction "I4_4") (pintype "bidirectional"))
    )
    (net (code "24") (name "Net-(IC1-GP4)") (class "Default")
      (node (ref "IC1") (pin "9") (pinfunction "GP4_9") (pintype "bidirectional"))
      (node (ref "IC5") (pin "5") (pinfunction "I5_5") (pintype "bidirectional"))
    )
    (net (code "25") (name "Net-(IC1-GP5)") (class "Default")
      (node (ref "IC1") (pin "10") (pinfunction "GP5_10") (pintype "bidirectional"))
      (node (ref "IC5") (pin "6") (pinfunction "I6_6") (pintype "bidirectional"))
    )
    (net (code "26") (name "Net-(IC1-GP6)") (class "Default")
      (node (ref "IC1") (pin "11") (pinfunction "GP6_11") (pintype "bidirectional"))
      (node (ref "IC5") (pin "7") (pinfunction "I7_7") (pintype "bidirectional"))
    )
    (net (code "27") (name "Net-(IC1-GP7)") (class "Default")
      (node (ref "IC1") (pin "12") (pinfunction "GP7_12") (pintype "bidirectional"))
      (node (ref "IC5") (pin "8") (pinfunction "I8_8") (pintype "bidirectional"))
    )
    (net (code "28") (name "Net-(IC1-~{RESET})") (class "Default")
      (node (ref "IC1") (pin "13") (pinfunction "~{RESET}_13") (pintype "bidirectional"))
      (node (ref "R13") (pin "3") (pinfunction "2_3") (pintype "passive"))
    )
    (net (code "29") (name "Net-(IC2-A0)") (class "Default")
      (node (ref "IC2") (pin "1") (pinfunction "A0_1") (pintype "bidirectional"))
      (node (ref "R6") (pin "3") (pinfunction "2_3") (pintype "passive"))
    )
    (net (code "30") (name "Net-(IC2-A1)") (class "Default")
      (node (ref "IC2") (pin "2") (pinfunction "A1_2") (pintype "bidirectional"))
      (node (ref "R5") (pin "3") (pinfunction "2_3") (pintype "passive"))
    )
    (net (code "31") (name "Net-(IC2-A2)") (class "Default")
      (node (ref "IC2") (pin "3") (pinfunction "A2_3") (pintype "bidirectional"))
      (node (ref "R18") (pin "2") (pinfunction "2_2") (pintype "passive"))
      (node (ref "R4") (pin "3") (pinfunction "2_3") (pintype "passive"))
    )
    (net (code "32") (name "Net-(IC2-GP0)") (class "Default")
      (node (ref "IC2") (pin "4") (pinfunction "GP0_4") (pintype "bidirectional"))
      (node (ref "IC6") (pin "1") (pinfunction "I1_1") (pintype "bidirectional"))
    )
    (net (code "33") (name "Net-(IC2-GP1)") (class "Default")
      (node (ref "IC2") (pin "5") (pinfunction "GP1_5") (pintype "bidirectional"))
      (node (ref "IC6") (pin "2") (pinfunction "I2_2") (pintype "bidirectional"))
    )
    (net (code "34") (name "Net-(IC2-GP2)") (class "Default")
      (node (ref "IC2") (pin "6") (pinfunction "GP2_6") (pintype "bidirectional"))
      (node (ref "IC6") (pin "3") (pinfunction "I3_3") (pintype "bidirectional"))
    )
    (net (code "35") (name "Net-(IC2-GP3)") (class "Default")
      (node (ref "IC2") (pin "7") (pinfunction "GP3_7") (pintype "bidirectional"))
      (node (ref "IC6") (pin "4") (pinfunction "I4_4") (pintype "bidirectional"))
    )
    (net (code "36") (name "Net-(IC2-GP4)") (class "Default")
      (node (ref "IC2") (pin "9") (pinfunction "GP4_9") (pintype "bidirectional"))
      (node (ref "IC6") (pin "5") (pinfunction "I5_5") (pintype "bidirectional"))
    )
    (net (code "37") (name "Net-(IC2-GP5)") (class "Default")
      (node (ref "IC2") (pin "10") (pinfunction "GP5_10") (pintype "bidirectional"))
      (node (ref "IC6") (pin "6") (pinfunction "I6_6") (pintype "bidirectional"))
    )
    (net (code "38") (name "Net-(IC2-GP6)") (class "Default")
      (node (ref "IC2") (pin "11") (pinfunction "GP6_11") (pintype "bidirectional"))
      (node (ref "IC6") (pin "7") (pinfunction "I7_7") (pintype "bidirectional"))
    )
    (net (code "39") (name "Net-(IC2-GP7)") (class "Default")
      (node (ref "IC2") (pin "12") (pinfunction "GP7_12") (pintype "bidirectional"))
      (node (ref "IC6") (pin "8") (pinfunction "I8_8") (pintype "bidirectional"))
    )
    (net (code "40") (name "Net-(IC2-~{RESET})") (class "Default")
      (node (ref "IC2") (pin "13") (pinfunction "~{RESET}_13") (pintype "bidirectional"))
      (node (ref "R14") (pin "3") (pinfunction "2_3") (pintype "passive"))
    )
    (net (code "41") (name "Net-(IC3-A0)") (class "Default")
      (node (ref "IC3") (pin "1") (pinfunction "A0_1") (pintype "bidirectional"))
      (node (ref "R9") (pin "3") (pinfunction "2_3") (pintype "passive"))
    )
    (net (code "42") (name "Net-(IC3-A1)") (class "Default")
      (node (ref "IC3") (pin "2") (pinfunction "A1_2") (pintype "bidirectional"))
      (node (ref "R8") (pin "3") (pinfunction "2_3") (pintype "passive"))
    )
    (net (code "43") (name "Net-(IC3-A2)") (class "Default")
      (node (ref "IC3") (pin "3") (pinfunction "A2_3") (pintype "bidirectional"))
      (node (ref "R19") (pin "2") (pinfunction "2_2") (pintype "passive"))
      (node (ref "R7") (pin "3") (pinfunction "2_3") (pintype "passive"))
    )
    (net (code "44") (name "Net-(IC3-GP0)") (class "Default")
      (node (ref "IC3") (pin "4") (pinfunction "GP0_4") (pintype "bidirectional"))
      (node (ref "IC7") (pin "1") (pinfunction "I1_1") (pintype "bidirectional"))
    )
    (net (code "45") (name "Net-(IC3-GP1)") (class "Default")
      (node (ref "IC3") (pin "5") (pinfunction "GP1_5") (pintype "bidirectional"))
      (node (ref "IC7") (pin "2") (pinfunction "I2_2") (pintype "bidirectional"))
    )
    (net (code "46") (name "Net-(IC3-GP2)") (class "Default")
      (node (ref "IC3") (pin "6") (pinfunction "GP2_6") (pintype "bidirectional"))
      (node (ref "IC7") (pin "3") (pinfunction "I3_3") (pintype "bidirectional"))
    )
    (net (code "47") (name "Net-(IC3-GP3)") (class "Default")
      (node (ref "IC3") (pin "7") (pinfunction "GP3_7") (pintype "bidirectional"))
      (node (ref "IC7") (pin "4") (pinfunction "I4_4") (pintype "bidirectional"))
    )
    (net (code "48") (name "Net-(IC3-GP4)") (class "Default")
      (node (ref "IC3") (pin "9") (pinfunction "GP4_9") (pintype "bidirectional"))
      (node (ref "IC7") (pin "5") (pinfunction "I5_5") (pintype "bidirectional"))
    )
    (net (code "49") (name "Net-(IC3-GP5)") (class "Default")
      (node (ref "IC3") (pin "10") (pinfunction "GP5_10") (pintype "bidirectional"))
      (node (ref "IC7") (pin "6") (pinfunction "I6_6") (pintype "bidirectional"))
    )
    (net (code "50") (name "Net-(IC3-GP6)") (class "Default")
      (node (ref "IC3") (pin "11") (pinfunction "GP6_11") (pintype "bidirectional"))
      (node (ref "IC7") (pin "7") (pinfunction "I7_7") (pintype "bidirectional"))
    )
    (net (code "51") (name "Net-(IC3-GP7)") (class "Default")
      (node (ref "IC3") (pin "12") (pinfunction "GP7_12") (pintype "bidirectional"))
      (node (ref "IC7") (pin "8") (pinfunction "I8_8") (pintype "bidirectional"))
    )
    (net (code "52") (name "Net-(IC3-~{RESET})") (class "Default")
      (node (ref "IC3") (pin "13") (pinfunction "~{RESET}_13") (pintype "bidirectional"))
      (node (ref "R15") (pin "3") (pinfunction "2_3") (pintype "passive"))
    )
    (net (code "53") (name "Net-(IC4-A0)") (class "Default")
      (node (ref "IC4") (pin "1") (pinfunction "A0_1") (pintype "bidirectional"))
      (node (ref "R12") (pin "3") (pinfunction "2_3") (pintype "passive"))
    )
    (net (code "54") (name "Net-(IC4-A1)") (class "Default")
      (node (ref "IC4") (pin "2") (pinfunction "A1_2") (pintype "bidirectional"))
      (node (ref "R11") (pin "3") (pinfunction "2_3") (pintype "passive"))
    )
    (net (code "55") (name "Net-(IC4-A2)") (class "Default")
      (node (ref "IC4") (pin "3") (pinfunction "A2_3") (pintype "bidirectional"))
      (node (ref "R10") (pin "3") (pinfunction "2_3") (pintype "passive"))
      (node (ref "R20") (pin "2") (pinfunction "2_2") (pintype "passive"))
    )
    (net (code "56") (name "Net-(IC4-GP0)") (class "Default")
      (node (ref "IC4") (pin "4") (pinfunction "GP0_4") (pintype "bidirectional"))
      (node (ref "IC8") (pin "1") (pinfunction "I1_1") (pintype "bidirectional"))
    )
    (net (code "57") (name "Net-(IC4-GP1)") (class "Default")
      (node (ref "IC4") (pin "5") (pinfunction "GP1_5") (pintype "bidirectional"))
      (node (ref "IC8") (pin "2") (pinfunction "I2_2") (pintype "bidirectional"))
    )
    (net (code "58") (name "Net-(IC4-GP2)") (class "Default")
      (node (ref "IC4") (pin "6") (pinfunction "GP2_6") (pintype "bidirectional"))
      (node (ref "IC8") (pin "3") (pinfunction "I3_3") (pintype "bidirectional"))
    )
    (net (code "59") (name "Net-(IC4-GP3)") (class "Default")
      (node (ref "IC4") (pin "7") (pinfunction "GP3_7") (pintype "bidirectional"))
      (node (ref "IC8") (pin "4") (pinfunction "I4_4") (pintype "bidirectional"))
    )
    (net (code "60") (name "Net-(IC4-GP4)") (class "Default")
      (node (ref "IC4") (pin "9") (pinfunction "GP4_9") (pintype "bidirectional"))
      (node (ref "IC8") (pin "5") (pinfunction "I5_5") (pintype "bidirectional"))
    )
    (net (code "61") (name "Net-(IC4-GP5)") (class "Default")
      (node (ref "IC4") (pin "10") (pinfunction "GP5_10") (pintype "bidirectional"))
      (node (ref "IC8") (pin "6") (pinfunction "I6_6") (pintype "bidirectional"))
    )
    (net (code "62") (name "Net-(IC4-GP6)") (class "Default")
      (node (ref "IC4") (pin "11") (pinfunction "GP6_11") (pintype "bidirectional"))
      (node (ref "IC8") (pin "7") (pinfunction "I7_7") (pintype "bidirectional"))
    )
    (net (code "63") (name "Net-(IC4-GP7)") (class "Default")
      (node (ref "IC4") (pin "12") (pinfunction "GP7_12") (pintype "bidirectional"))
      (node (ref "IC8") (pin "8") (pinfunction "I8_8") (pintype "bidirectional"))
    )
    (net (code "64") (name "Net-(IC4-~{RESET})") (class "Default")
      (node (ref "IC4") (pin "13") (pinfunction "~{RESET}_13") (pintype "bidirectional"))
      (node (ref "R16") (pin "3") (pinfunction "2_3") (pintype "passive"))
    )
    (net (code "65") (name "Net-(IC5-O1)") (class "Default")
      (node (ref "IC5") (pin "18") (pinfunction "O1_18") (pintype "bidirectional"))
      (node (ref "RL8") (pin "12") (pinfunction "2_12") (pintype "passive"))
    )
    (net (code "66") (name "Net-(IC5-O2)") (class "Default")
      (node (ref "IC5") (pin "17") (pinfunction "O2_17") (pintype "bidirectional"))
      (node (ref "RL7") (pin "12") (pinfunction "2_12") (pintype "passive"))
    )
    (net (code "67") (name "Net-(IC5-O3)") (class "Default")
      (node (ref "IC5") (pin "16") (pinfunction "O3_16") (pintype "bidirectional"))
      (node (ref "RL6") (pin "12") (pinfunction "2_12") (pintype "passive"))
    )
    (net (code "68") (name "Net-(IC5-O4)") (class "Default")
      (node (ref "IC5") (pin "15") (pinfunction "O4_15") (pintype "bidirectional"))
      (node (ref "RL5") (pin "12") (pinfunction "2_12") (pintype "passive"))
    )
    (net (code "69") (name "Net-(IC5-O5)") (class "Default")
      (node (ref "IC5") (pin "14") (pinfunction "O5_14") (pintype "bidirectional"))
      (node (ref "RL4") (pin "12") (pinfunction "2_12") (pintype "passive"))
    )
    (net (code "70") (name "Net-(IC5-O6)") (class "Default")
      (node (ref "IC5") (pin "13") (pinfunction "O6_13") (pintype "bidirectional"))
      (node (ref "RL3") (pin "12") (pinfunction "2_12") (pintype "passive"))
    )
    (net (code "71") (name "Net-(IC5-O7)") (class "Default")
      (node (ref "IC5") (pin "12") (pinfunction "O7_12") (pintype "bidirectional"))
      (node (ref "RL2") (pin "12") (pinfunction "2_12") (pintype "passive"))
    )
    (net (code "72") (name "Net-(IC5-O8)") (class "Default")
      (node (ref "IC5") (pin "11") (pinfunction "O8_11") (pintype "bidirectional"))
      (node (ref "RL1") (pin "12") (pinfunction "2_12") (pintype "passive"))
    )
    (net (code "73") (name "Net-(IC6-O1)") (class "Default")
      (node (ref "IC6") (pin "18") (pinfunction "O1_18") (pintype "bidirectional"))
      (node (ref "RL16") (pin "12") (pinfunction "2_12") (pintype "passive"))
    )
    (net (code "74") (name "Net-(IC6-O2)") (class "Default")
      (node (ref "IC6") (pin "17") (pinfunction "O2_17") (pintype "bidirectional"))
      (node (ref "RL15") (pin "12") (pinfunction "2_12") (pintype "passive"))
    )
    (net (code "75") (name "Net-(IC6-O3)") (class "Default")
      (node (ref "IC6") (pin "16") (pinfunction "O3_16") (pintype "bidirectional"))
      (node (ref "RL14") (pin "12") (pinfunction "2_12") (pintype "passive"))
    )
    (net (code "76") (name "Net-(IC6-O4)") (class "Default")
      (node (ref "IC6") (pin "15") (pinfunction "O4_15") (pintype "bidirectional"))
      (node (ref "RL13") (pin "12") (pinfunction "2_12") (pintype "passive"))
    )
    (net (code "77") (name "Net-(IC6-O5)") (class "Default")
      (node (ref "IC6") (pin "14") (pinfunction "O5_14") (pintype "bidirectional"))
      (node (ref "RL12") (pin "12") (pinfunction "2_12") (pintype "passive"))
    )
    (net (code "78") (name "Net-(IC6-O6)") (class "Default")
      (node (ref "IC6") (pin "13") (pinfunction "O6_13") (pintype "bidirectional"))
      (node (ref "RL11") (pin "12") (pinfunction "2_12") (pintype "passive"))
    )
    (net (code "79") (name "Net-(IC6-O7)") (class "Default")
      (node (ref "IC6") (pin "12") (pinfunction "O7_12") (pintype "bidirectional"))
      (node (ref "RL10") (pin "12") (pinfunction "2_12") (pintype "passive"))
    )
    (net (code "80") (name "Net-(IC6-O8)") (class "Default")
      (node (ref "IC6") (pin "11") (pinfunction "O8_11") (pintype "bidirectional"))
      (node (ref "RL9") (pin "12") (pinfunction "2_12") (pintype "passive"))
    )
    (net (code "81") (name "Net-(IC7-O1)") (class "Default")
      (node (ref "IC7") (pin "18") (pinfunction "O1_18") (pintype "bidirectional"))
      (node (ref "RL24") (pin "12") (pinfunction "2_12") (pintype "passive"))
    )
    (net (code "82") (name "Net-(IC7-O2)") (class "Default")
      (node (ref "IC7") (pin "17") (pinfunction "O2_17") (pintype "bidirectional"))
      (node (ref "RL23") (pin "12") (pinfunction "2_12") (pintype "passive"))
    )
    (net (code "83") (name "Net-(IC7-O3)") (class "Default")
      (node (ref "IC7") (pin "16") (pinfunction "O3_16") (pintype "bidirectional"))
      (node (ref "RL22") (pin "12") (pinfunction "2_12") (pintype "passive"))
    )
    (net (code "84") (name "Net-(IC7-O4)") (class "Default")
      (node (ref "IC7") (pin "15") (pinfunction "O4_15") (pintype "bidirectional"))
      (node (ref "RL21") (pin "12") (pinfunction "2_12") (pintype "passive"))
    )
    (net (code "85") (name "Net-(IC7-O5)") (class "Default")
      (node (ref "IC7") (pin "14") (pinfunction "O5_14") (pintype "bidirectional"))
      (node (ref "RL20") (pin "12") (pinfunction "2_12") (pintype "passive"))
    )
    (net (code "86") (name "Net-(IC7-O6)") (class "Default")
      (node (ref "IC7") (pin "13") (pinfunction "O6_13") (pintype "bidirectional"))
      (node (ref "RL19") (pin "12") (pinfunction "2_12") (pintype "passive"))
    )
    (net (code "87") (name "Net-(IC7-O7)") (class "Default")
      (node (ref "IC7") (pin "12") (pinfunction "O7_12") (pintype "bidirectional"))
      (node (ref "RL18") (pin "12") (pinfunction "2_12") (pintype "passive"))
    )
    (net (code "88") (name "Net-(IC7-O8)") (class "Default")
      (node (ref "IC7") (pin "11") (pinfunction "O8_11") (pintype "bidirectional"))
      (node (ref "RL17") (pin "12") (pinfunction "2_12") (pintype "passive"))
    )
    (net (code "89") (name "Net-(IC8-O1)") (class "Default")
      (node (ref "IC8") (pin "18") (pinfunction "O1_18") (pintype "bidirectional"))
      (node (ref "RL32") (pin "12") (pinfunction "2_12") (pintype "passive"))
    )
    (net (code "90") (name "Net-(IC8-O2)") (class "Default")
      (node (ref "IC8") (pin "17") (pinfunction "O2_17") (pintype "bidirectional"))
      (node (ref "RL31") (pin "12") (pinfunction "2_12") (pintype "passive"))
    )
    (net (code "91") (name "Net-(IC8-O3)") (class "Default")
      (node (ref "IC8") (pin "16") (pinfunction "O3_16") (pintype "bidirectional"))
      (node (ref "RL30") (pin "12") (pinfunction "2_12") (pintype "passive"))
    )
    (net (code "92") (name "Net-(IC8-O4)") (class "Default")
      (node (ref "IC8") (pin "15") (pinfunction "O4_15") (pintype "bidirectional"))
      (node (ref "RL29") (pin "12") (pinfunction "2_12") (pintype "passive"))
    )
    (net (code "93") (name "Net-(IC8-O5)") (class "Default")
      (node (ref "IC8") (pin "14") (pinfunction "O5_14") (pintype "bidirectional"))
      (node (ref "RL28") (pin "12") (pinfunction "2_12") (pintype "passive"))
    )
    (net (code "94") (name "Net-(IC8-O6)") (class "Default")
      (node (ref "IC8") (pin "13") (pinfunction "O6_13") (pintype "bidirectional"))
      (node (ref "RL27") (pin "12") (pinfunction "2_12") (pintype "passive"))
    )
    (net (code "95") (name "Net-(IC8-O7)") (class "Default")
      (node (ref "IC8") (pin "12") (pinfunction "O7_12") (pintype "bidirectional"))
      (node (ref "RL26") (pin "12") (pinfunction "2_12") (pintype "passive"))
    )
    (net (code "96") (name "Net-(IC8-O8)") (class "Default")
      (node (ref "IC8") (pin "11") (pinfunction "O8_11") (pintype "bidirectional"))
      (node (ref "RL25") (pin "12") (pinfunction "2_12") (pintype "passive"))
    )
    (net (code "97") (name "Net-(RL1B-COM)") (class "Default")
      (node (ref "CON2") (pin "1") (pinfunction "1_1") (pintype "passive"))
      (node (ref "RL1") (pin "4") (pinfunction "COM_4") (pintype "passive"))
      (node (ref "RL2") (pin "4") (pinfunction "COM_4") (pintype "passive"))
      (node (ref "RL3") (pin "4") (pinfunction "COM_4") (pintype "passive"))
      (node (ref "RL4") (pin "4") (pinfunction "COM_4") (pintype "passive"))
      (node (ref "RL5") (pin "4") (pinfunction "COM_4") (pintype "passive"))
      (node (ref "RL6") (pin "4") (pinfunction "COM_4") (pintype "passive"))
      (node (ref "RL7") (pin "4") (pinfunction "COM_4") (pintype "passive"))
      (node (ref "RL8") (pin "4") (pinfunction "COM_4") (pintype "passive"))
    )
    (net (code "98") (name "Net-(RL10B-COM)") (class "Default")
      (node (ref "CON3") (pin "1") (pinfunction "1_1") (pintype "passive"))
      (node (ref "RL10") (pin "4") (pinfunction "COM_4") (pintype "passive"))
      (node (ref "RL11") (pin "4") (pinfunction "COM_4") (pintype "passive"))
      (node (ref "RL12") (pin "4") (pinfunction "COM_4") (pintype "passive"))
      (node (ref "RL13") (pin "4") (pinfunction "COM_4") (pintype "passive"))
      (node (ref "RL14") (pin "4") (pinfunction "COM_4") (pintype "passive"))
      (node (ref "RL15") (pin "4") (pinfunction "COM_4") (pintype "passive"))
      (node (ref "RL16") (pin "4") (pinfunction "COM_4") (pintype "passive"))
      (node (ref "RL9") (pin "4") (pinfunction "COM_4") (pintype "passive"))
    )
    (net (code "99") (name "Net-(RL10B-NO)") (class "Default")
      (node (ref "CON7") (pin "1") (pinfunction "1_1") (pintype "passive"))
      (node (ref "RL10") (pin "5") (pinfunction "NO_5") (pintype "passive"))
      (node (ref "RL18") (pin "5") (pinfunction "NO_5") (pintype "passive"))
      (node (ref "RL2") (pin "5") (pinfunction "NO_5") (pintype "passive"))
      (node (ref "RL26") (pin "5") (pinfunction "NO_5") (pintype "passive"))
    )
    (net (code "100") (name "Net-(RL11B-NO)") (class "Default")
      (node (ref "CON8") (pin "1") (pinfunction "1_1") (pintype "passive"))
      (node (ref "RL11") (pin "5") (pinfunction "NO_5") (pintype "passive"))
      (node (ref "RL19") (pin "5") (pinfunction "NO_5") (pintype "passive"))
      (node (ref "RL27") (pin "5") (pinfunction "NO_5") (pintype "passive"))
      (node (ref "RL3") (pin "5") (pinfunction "NO_5") (pintype "passive"))
    )
    (net (code "101") (name "Net-(RL12B-NO)") (class "Default")
      (node (ref "CON9") (pin "1") (pinfunction "1_1") (pintype "passive"))
      (node (ref "RL12") (pin "5") (pinfunction "NO_5") (pintype "passive"))
      (node (ref "RL20") (pin "5") (pinfunction "NO_5") (pintype "passive"))
      (node (ref "RL28") (pin "5") (pinfunction "NO_5") (pintype "passive"))
      (node (ref "RL4") (pin "5") (pinfunction "NO_5") (pintype "passive"))
    )
    (net (code "102") (name "Net-(RL13B-NO)") (class "Default")
      (node (ref "CON10") (pin "1") (pinfunction "1_1") (pintype "passive"))
      (node (ref "RL13") (pin "5") (pinfunction "NO_5") (pintype "passive"))
      (node (ref "RL21") (pin "5") (pinfunction "NO_5") (pintype "passive"))
      (node (ref "RL29") (pin "5") (pinfunction "NO_5") (pintype "passive"))
      (node (ref "RL5") (pin "5") (pinfunction "NO_5") (pintype "passive"))
    )
    (net (code "103") (name "Net-(RL14B-NO)") (class "Default")
      (node (ref "CON11") (pin "1") (pinfunction "1_1") (pintype "passive"))
      (node (ref "RL14") (pin "5") (pinfunction "NO_5") (pintype "passive"))
      (node (ref "RL22") (pin "5") (pinfunction "NO_5") (pintype "passive"))
      (node (ref "RL30") (pin "5") (pinfunction "NO_5") (pintype "passive"))
      (node (ref "RL6") (pin "5") (pinfunction "NO_5") (pintype "passive"))
    )
    (net (code "104") (name "Net-(RL15B-NO)") (class "Default")
      (node (ref "CON12") (pin "1") (pinfunction "1_1") (pintype "passive"))
      (node (ref "RL15") (pin "5") (pinfunction "NO_5") (pintype "passive"))
      (node (ref "RL23") (pin "5") (pinfunction "NO_5") (pintype "passive"))
      (node (ref "RL31") (pin "5") (pinfunction "NO_5") (pintype "passive"))
      (node (ref "RL7") (pin "5") (pinfunction "NO_5") (pintype "passive"))
    )
    (net (code "105") (name "Net-(RL16B-NO)") (class "Default")
      (node (ref "CON13") (pin "1") (pinfunction "1_1") (pintype "passive"))
      (node (ref "RL16") (pin "5") (pinfunction "NO_5") (pintype "passive"))
      (node (ref "RL24") (pin "5") (pinfunction "NO_5") (pintype "passive"))
      (node (ref "RL32") (pin "5") (pinfunction "NO_5") (pintype "passive"))
      (node (ref "RL8") (pin "5") (pinfunction "NO_5") (pintype "passive"))
    )
    (net (code "106") (name "Net-(RL17B-COM)") (class "Default")
      (node (ref "CON4") (pin "1") (pinfunction "1_1") (pintype "passive"))
      (node (ref "RL17") (pin "4") (pinfunction "COM_4") (pintype "passive"))
      (node (ref "RL18") (pin "4") (pinfunction "COM_4") (pintype "passive"))
      (node (ref "RL19") (pin "4") (pinfunction "COM_4") (pintype "passive"))
      (node (ref "RL20") (pin "4") (pinfunction "COM_4") (pintype "passive"))
      (node (ref "RL21") (pin "4") (pinfunction "COM_4") (pintype "passive"))
      (node (ref "RL22") (pin "4") (pinfunction "COM_4") (pintype "passive"))
      (node (ref "RL23") (pin "4") (pinfunction "COM_4") (pintype "passive"))
      (node (ref "RL24") (pin "4") (pinfunction "COM_4") (pintype "passive"))
    )
    (net (code "107") (name "Net-(RL17B-NO)") (class "Default")
      (node (ref "CON6") (pin "1") (pinfunction "1_1") (pintype "passive"))
      (node (ref "RL1") (pin "5") (pinfunction "NO_5") (pintype "passive"))
      (node (ref "RL17") (pin "5") (pinfunction "NO_5") (pintype "passive"))
      (node (ref "RL25") (pin "5") (pinfunction "NO_5") (pintype "passive"))
      (node (ref "RL9") (pin "5") (pinfunction "NO_5") (pintype "passive"))
    )
    (net (code "108") (name "Net-(RL25B-COM)") (class "Default")
      (node (ref "CON5") (pin "1") (pinfunction "1_1") (pintype "passive"))
      (node (ref "RL25") (pin "4") (pinfunction "COM_4") (pintype "passive"))
      (node (ref "RL26") (pin "4") (pinfunction "COM_4") (pintype "passive"))
      (node (ref "RL27") (pin "4") (pinfunction "COM_4") (pintype "passive"))
      (node (ref "RL28") (pin "4") (pinfunction "COM_4") (pintype "passive"))
      (node (ref "RL29") (pin "4") (pinfunction "COM_4") (pintype "passive"))
      (node (ref "RL30") (pin "4") (pinfunction "COM_4") (pintype "passive"))
      (node (ref "RL31") (pin "4") (pinfunction "COM_4") (pintype "passive"))
      (node (ref "RL32") (pin "4") (pinfunction "COM_4") (pintype "passive"))
    )
    (net (code "109") (name "VCC") (class "Default")
      (node (ref "C1") (pin "1") (pinfunction "1_1") (pintype "passive"))
      (node (ref "C2") (pin "1") (pinfunction "1_1") (pintype "passive"))
      (node (ref "C3") (pin "1") (pinfunction "1_1") (pintype "passive"))
      (node (ref "C4") (pin "1") (pinfunction "1_1") (pintype "passive"))
      (node (ref "CON1") (pin "1") (pinfunction "1_1") (pintype "passive"))
      (node (ref "IC1") (pin "16") (pinfunction "VDD_16") (pintype "power_in"))
      (node (ref "IC2") (pin "16") (pinfunction "VDD_16") (pintype "power_in"))
      (node (ref "IC3") (pin "16") (pinfunction "VDD_16") (pintype "power_in"))
      (node (ref "IC4") (pin "16") (pinfunction "VDD_16") (pintype "power_in"))
      (node (ref "R11") (pin "1") (pinfunction "1_1") (pintype "passive"))
      (node (ref "R11") (pin "2") (pinfunction "1_2") (pintype "passive"))
      (node (ref "R12") (pin "1") (pinfunction "1_1") (pintype "passive"))
      (node (ref "R12") (pin "2") (pinfunction "1_2") (pintype "passive"))
      (node (ref "R13") (pin "1") (pinfunction "1_1") (pintype "passive"))
      (node (ref "R13") (pin "2") (pinfunction "1_2") (pintype "passive"))
      (node (ref "R14") (pin "1") (pinfunction "1_1") (pintype "passive"))
      (node (ref "R14") (pin "2") (pinfunction "1_2") (pintype "passive"))
      (node (ref "R15") (pin "1") (pinfunction "1_1") (pintype "passive"))
      (node (ref "R15") (pin "2") (pinfunction "1_2") (pintype "passive"))
      (node (ref "R16") (pin "1") (pinfunction "1_1") (pintype "passive"))
      (node (ref "R16") (pin "2") (pinfunction "1_2") (pintype "passive"))
      (node (ref "R17") (pin "1") (pinfunction "1_1") (pintype "passive"))
      (node (ref "R18") (pin "1") (pinfunction "1_1") (pintype "passive"))
      (node (ref "R19") (pin "1") (pinfunction "1_1") (pintype "passive"))
      (node (ref "R20") (pin "1") (pinfunction "1_1") (pintype "passive"))
      (node (ref "R6") (pin "1") (pinfunction "1_1") (pintype "passive"))
      (node (ref "R6") (pin "2") (pinfunction "1_2") (pintype "passive"))
      (node (ref "R8") (pin "1") (pinfunction "1_1") (pintype "passive"))
      (node (ref "R8") (pin "2") (pinfunction "1_2") (pintype "passive"))
      (node (ref "X1") (pin "2") (pinfunction "1_2") (pintype "passive"))
    )
    (net (code "110") (name "unconnected-(CON2B-1-Pad2)") (class "Default")
      (node (ref "CON2") (pin "2") (pinfunction "1_2") (pintype "passive"))
    )
    (net (code "111") (name "unconnected-(CON3B-1-Pad2)") (class "Default")
      (node (ref "CON3") (pin "2") (pinfunction "1_2") (pintype "passive"))
    )
    (net (code "112") (name "unconnected-(CON4B-1-Pad2)") (class "Default")
      (node (ref "CON4") (pin "2") (pinfunction "1_2") (pintype "passive"))
    )
    (net (code "113") (name "unconnected-(CON5B-1-Pad2)") (class "Default")
      (node (ref "CON5") (pin "2") (pinfunction "1_2") (pintype "passive"))
    )
    (net (code "114") (name "unconnected-(CON6B-1-Pad2)") (class "Default")
      (node (ref "CON6") (pin "2") (pinfunction "1_2") (pintype "passive"))
    )
    (net (code "115") (name "unconnected-(CON7B-1-Pad2)") (class "Default")
      (node (ref "CON7") (pin "2") (pinfunction "1_2") (pintype "passive"))
    )
    (net (code "116") (name "unconnected-(CON8B-1-Pad2)") (class "Default")
      (node (ref "CON8") (pin "2") (pinfunction "1_2") (pintype "passive"))
    )
    (net (code "117") (name "unconnected-(CON9B-1-Pad2)") (class "Default")
      (node (ref "CON9") (pin "2") (pinfunction "1_2") (pintype "passive"))
    )
    (net (code "118") (name "unconnected-(CON10B-1-Pad2)") (class "Default")
      (node (ref "CON10") (pin "2") (pinfunction "1_2") (pintype "passive"))
    )
    (net (code "119") (name "unconnected-(CON11B-1-Pad2)") (class "Default")
      (node (ref "CON11") (pin "2") (pinfunction "1_2") (pintype "passive"))
    )
    (net (code "120") (name "unconnected-(CON12B-1-Pad2)") (class "Default")
      (node (ref "CON12") (pin "2") (pinfunction "1_2") (pintype "passive"))
    )
    (net (code "121") (name "unconnected-(CON13B-1-Pad2)") (class "Default")
      (node (ref "CON13") (pin "2") (pinfunction "1_2") (pintype "passive"))
    )
    (net (code "122") (name "unconnected-(RL1B-NC-Pad3)") (class "Default")
      (node (ref "RL1") (pin "3") (pinfunction "NC_3") (pintype "passive"))
    )
    (net (code "123") (name "unconnected-(RL1C-NC-Pad10)") (class "Default")
      (node (ref "RL1") (pin "10") (pinfunction "NC_10") (pintype "passive"))
    )
    (net (code "124") (name "unconnected-(RL2B-NC-Pad3)") (class "Default")
      (node (ref "RL2") (pin "3") (pinfunction "NC_3") (pintype "passive"))
    )
    (net (code "125") (name "unconnected-(RL2C-NC-Pad10)") (class "Default")
      (node (ref "RL2") (pin "10") (pinfunction "NC_10") (pintype "passive"))
    )
    (net (code "126") (name "unconnected-(RL3B-NC-Pad3)") (class "Default")
      (node (ref "RL3") (pin "3") (pinfunction "NC_3") (pintype "passive"))
    )
    (net (code "127") (name "unconnected-(RL3C-NC-Pad10)") (class "Default")
      (node (ref "RL3") (pin "10") (pinfunction "NC_10") (pintype "passive"))
    )
    (net (code "128") (name "unconnected-(RL4B-NC-Pad3)") (class "Default")
      (node (ref "RL4") (pin "3") (pinfunction "NC_3") (pintype "passive"))
    )
    (net (code "129") (name "unconnected-(RL4C-NC-Pad10)") (class "Default")
      (node (ref "RL4") (pin "10") (pinfunction "NC_10") (pintype "passive"))
    )
    (net (code "130") (name "unconnected-(RL5B-NC-Pad3)") (class "Default")
      (node (ref "RL5") (pin "3") (pinfunction "NC_3") (pintype "passive"))
    )
    (net (code "131") (name "unconnected-(RL5C-NC-Pad10)") (class "Default")
      (node (ref "RL5") (pin "10") (pinfunction "NC_10") (pintype "passive"))
    )
    (net (code "132") (name "unconnected-(RL6B-NC-Pad3)") (class "Default")
      (node (ref "RL6") (pin "3") (pinfunction "NC_3") (pintype "passive"))
    )
    (net (code "133") (name "unconnected-(RL6C-NC-Pad10)") (class "Default")
      (node (ref "RL6") (pin "10") (pinfunction "NC_10") (pintype "passive"))
    )
    (net (code "134") (name "unconnected-(RL7B-NC-Pad3)") (class "Default")
      (node (ref "RL7") (pin "3") (pinfunction "NC_3") (pintype "passive"))
    )
    (net (code "135") (name "unconnected-(RL7C-NC-Pad10)") (class "Default")
      (node (ref "RL7") (pin "10") (pinfunction "NC_10") (pintype "passive"))
    )
    (net (code "136") (name "unconnected-(RL8B-NC-Pad3)") (class "Default")
      (node (ref "RL8") (pin "3") (pinfunction "NC_3") (pintype "passive"))
    )
    (net (code "137") (name "unconnected-(RL8C-NC-Pad10)") (class "Default")
      (node (ref "RL8") (pin "10") (pinfunction "NC_10") (pintype "passive"))
    )
    (net (code "138") (name "unconnected-(RL9B-NC-Pad3)") (class "Default")
      (node (ref "RL9") (pin "3") (pinfunction "NC_3") (pintype "passive"))
    )
    (net (code "139") (name "unconnected-(RL9C-NC-Pad10)") (class "Default")
      (node (ref "RL9") (pin "10") (pinfunction "NC_10") (pintype "passive"))
    )
    (net (code "140") (name "unconnected-(RL10B-NC-Pad3)") (class "Default")
      (node (ref "RL10") (pin "3") (pinfunction "NC_3") (pintype "passive"))
    )
    (net (code "141") (name "unconnected-(RL10C-NC-Pad10)") (class "Default")
      (node (ref "RL10") (pin "10") (pinfunction "NC_10") (pintype "passive"))
    )
    (net (code "142") (name "unconnected-(RL11B-NC-Pad3)") (class "Default")
      (node (ref "RL11") (pin "3") (pinfunction "NC_3") (pintype "passive"))
    )
    (net (code "143") (name "unconnected-(RL11C-NC-Pad10)") (class "Default")
      (node (ref "RL11") (pin "10") (pinfunction "NC_10") (pintype "passive"))
    )
    (net (code "144") (name "unconnected-(RL12B-NC-Pad3)") (class "Default")
      (node (ref "RL12") (pin "3") (pinfunction "NC_3") (pintype "passive"))
    )
    (net (code "145") (name "unconnected-(RL12C-NC-Pad10)") (class "Default")
      (node (ref "RL12") (pin "10") (pinfunction "NC_10") (pintype "passive"))
    )
    (net (code "146") (name "unconnected-(RL13B-NC-Pad3)") (class "Default")
      (node (ref "RL13") (pin "3") (pinfunction "NC_3") (pintype "passive"))
    )
    (net (code "147") (name "unconnected-(RL13C-NC-Pad10)") (class "Default")
      (node (ref "RL13") (pin "10") (pinfunction "NC_10") (pintype "passive"))
    )
    (net (code "148") (name "unconnected-(RL14B-NC-Pad3)") (class "Default")
      (node (ref "RL14") (pin "3") (pinfunction "NC_3") (pintype "passive"))
    )
    (net (code "149") (name "unconnected-(RL14C-NC-Pad10)") (class "Default")
      (node (ref "RL14") (pin "10") (pinfunction "NC_10") (pintype "passive"))
    )
    (net (code "150") (name "unconnected-(RL15B-NC-Pad3)") (class "Default")
      (node (ref "RL15") (pin "3") (pinfunction "NC_3") (pintype "passive"))
    )
    (net (code "151") (name "unconnected-(RL15C-NC-Pad10)") (class "Default")
      (node (ref "RL15") (pin "10") (pinfunction "NC_10") (pintype "passive"))
    )
    (net (code "152") (name "unconnected-(RL16B-NC-Pad3)") (class "Default")
      (node (ref "RL16") (pin "3") (pinfunction "NC_3") (pintype "passive"))
    )
    (net (code "153") (name "unconnected-(RL16C-NC-Pad10)") (class "Default")
      (node (ref "RL16") (pin "10") (pinfunction "NC_10") (pintype "passive"))
    )
    (net (code "154") (name "unconnected-(RL17B-NC-Pad3)") (class "Default")
      (node (ref "RL17") (pin "3") (pinfunction "NC_3") (pintype "passive"))
    )
    (net (code "155") (name "unconnected-(RL17C-NC-Pad10)") (class "Default")
      (node (ref "RL17") (pin "10") (pinfunction "NC_10") (pintype "passive"))
    )
    (net (code "156") (name "unconnected-(RL18B-NC-Pad3)") (class "Default")
      (node (ref "RL18") (pin "3") (pinfunction "NC_3") (pintype "passive"))
    )
    (net (code "157") (name "unconnected-(RL18C-NC-Pad10)") (class "Default")
      (node (ref "RL18") (pin "10") (pinfunction "NC_10") (pintype "passive"))
    )
    (net (code "158") (name "unconnected-(RL19B-NC-Pad3)") (class "Default")
      (node (ref "RL19") (pin "3") (pinfunction "NC_3") (pintype "passive"))
    )
    (net (code "159") (name "unconnected-(RL19C-NC-Pad10)") (class "Default")
      (node (ref "RL19") (pin "10") (pinfunction "NC_10") (pintype "passive"))
    )
    (net (code "160") (name "unconnected-(RL20B-NC-Pad3)") (class "Default")
      (node (ref "RL20") (pin "3") (pinfunction "NC_3") (pintype "passive"))
    )
    (net (code "161") (name "unconnected-(RL20C-NC-Pad10)") (class "Default")
      (node (ref "RL20") (pin "10") (pinfunction "NC_10") (pintype "passive"))
    )
    (net (code "162") (name "unconnected-(RL21B-NC-Pad3)") (class "Default")
      (node (ref "RL21") (pin "3") (pinfunction "NC_3") (pintype "passive"))
    )
    (net (code "163") (name "unconnected-(RL21C-NC-Pad10)") (class "Default")
      (node (ref "RL21") (pin "10") (pinfunction "NC_10") (pintype "passive"))
    )
    (net (code "164") (name "unconnected-(RL22B-NC-Pad3)") (class "Default")
      (node (ref "RL22") (pin "3") (pinfunction "NC_3") (pintype "passive"))
    )
    (net (code "165") (name "unconnected-(RL22C-NC-Pad10)") (class "Default")
      (node (ref "RL22") (pin "10") (pinfunction "NC_10") (pintype "passive"))
    )
    (net (code "166") (name "unconnected-(RL23B-NC-Pad3)") (class "Default")
      (node (ref "RL23") (pin "3") (pinfunction "NC_3") (pintype "passive"))
    )
    (net (code "167") (name "unconnected-(RL23C-NC-Pad10)") (class "Default")
      (node (ref "RL23") (pin "10") (pinfunction "NC_10") (pintype "passive"))
    )
    (net (code "168") (name "unconnected-(RL24B-NC-Pad3)") (class "Default")
      (node (ref "RL24") (pin "3") (pinfunction "NC_3") (pintype "passive"))
    )
    (net (code "169") (name "unconnected-(RL24C-NC-Pad10)") (class "Default")
      (node (ref "RL24") (pin "10") (pinfunction "NC_10") (pintype "passive"))
    )
    (net (code "170") (name "unconnected-(RL25B-NC-Pad3)") (class "Default")
      (node (ref "RL25") (pin "3") (pinfunction "NC_3") (pintype "passive"))
    )
    (net (code "171") (name "unconnected-(RL25C-NC-Pad10)") (class "Default")
      (node (ref "RL25") (pin "10") (pinfunction "NC_10") (pintype "passive"))
    )
    (net (code "172") (name "unconnected-(RL26B-NC-Pad3)") (class "Default")
      (node (ref "RL26") (pin "3") (pinfunction "NC_3") (pintype "passive"))
    )
    (net (code "173") (name "unconnected-(RL26C-NC-Pad10)") (class "Default")
      (node (ref "RL26") (pin "10") (pinfunction "NC_10") (pintype "passive"))
    )
    (net (code "174") (name "unconnected-(RL27B-NC-Pad3)") (class "Default")
      (node (ref "RL27") (pin "3") (pinfunction "NC_3") (pintype "passive"))
    )
    (net (code "175") (name "unconnected-(RL27C-NC-Pad10)") (class "Default")
      (node (ref "RL27") (pin "10") (pinfunction "NC_10") (pintype "passive"))
    )
    (net (code "176") (name "unconnected-(RL28B-NC-Pad3)") (class "Default")
      (node (ref "RL28") (pin "3") (pinfunction "NC_3") (pintype "passive"))
    )
    (net (code "177") (name "unconnected-(RL28C-NC-Pad10)") (class "Default")
      (node (ref "RL28") (pin "10") (pinfunction "NC_10") (pintype "passive"))
    )
    (net (code "178") (name "unconnected-(RL29B-NC-Pad3)") (class "Default")
      (node (ref "RL29") (pin "3") (pinfunction "NC_3") (pintype "passive"))
    )
    (net (code "179") (name "unconnected-(RL29C-NC-Pad10)") (class "Default")
      (node (ref "RL29") (pin "10") (pinfunction "NC_10") (pintype "passive"))
    )
    (net (code "180") (name "unconnected-(RL30B-NC-Pad3)") (class "Default")
      (node (ref "RL30") (pin "3") (pinfunction "NC_3") (pintype "passive"))
    )
    (net (code "181") (name "unconnected-(RL30C-NC-Pad10)") (class "Default")
      (node (ref "RL30") (pin "10") (pinfunction "NC_10") (pintype "passive"))
    )
    (net (code "182") (name "unconnected-(RL31B-NC-Pad3)") (class "Default")
      (node (ref "RL31") (pin "3") (pinfunction "NC_3") (pintype "passive"))
    )
    (net (code "183") (name "unconnected-(RL31C-NC-Pad10)") (class "Default")
      (node (ref "RL31") (pin "10") (pinfunction "NC_10") (pintype "passive"))
    )
    (net (code "184") (name "unconnected-(RL32B-NC-Pad3)") (class "Default")
      (node (ref "RL32") (pin "3") (pinfunction "NC_3") (pintype "passive"))
    )
    (net (code "185") (name "unconnected-(RL32C-NC-Pad10)") (class "Default")
      (node (ref "RL32") (pin "10") (pinfunction "NC_10") (pintype "passive"))
    )
  )
)
